# FRONT_PWR.net
KiCad netlist of a schematic drawn in Altium Designer
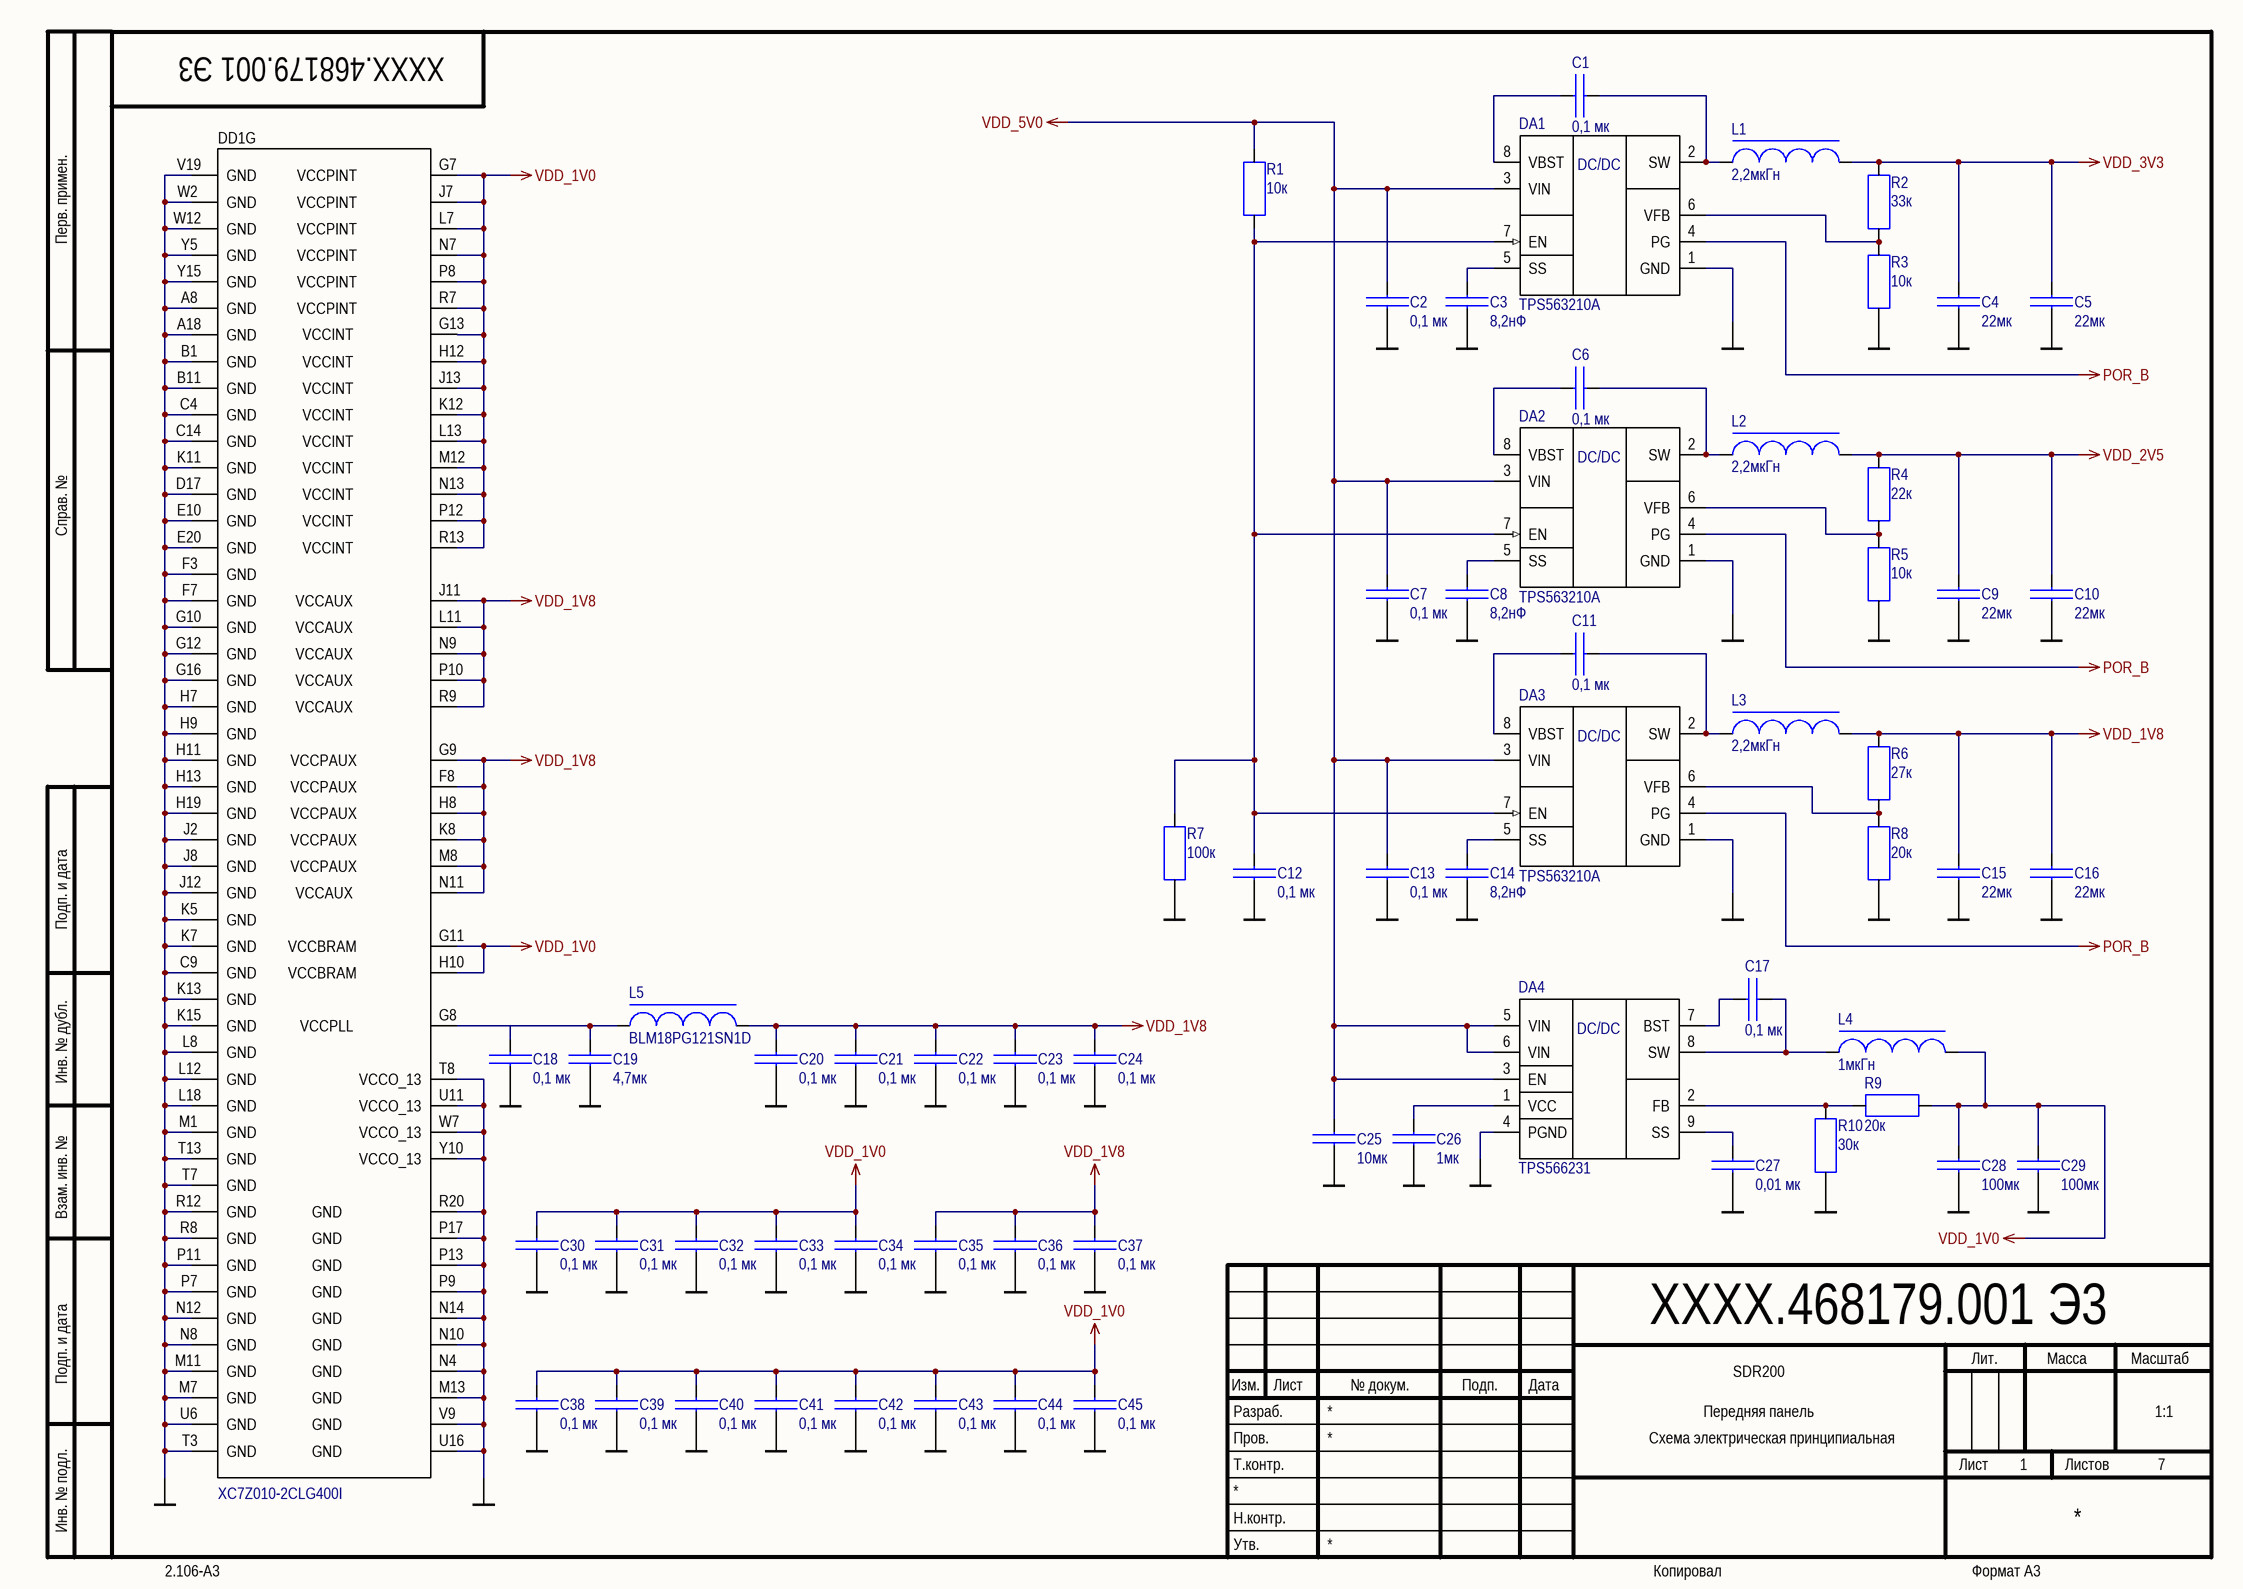
[diagram p0: FRONT_PWR.SchDoc]

(export (version "E")
  (design (tool "Eeschema 10.0.6"))
  (components
    (comp (ref "C1")
      (value "CC0402KRX5R6BB104")
      (footprint "CAPC1005X05L")
      (description "ЧИП конденсатор")
      (fields
        (field (name "NOMINAL") "0,1 мк")
        (field (name "MANUFACTURER") "Yageo")
        (field (name "TOLERANCE") "10%")
      )
      (libsource (lib "Database_Gost") (part "Capacitor const"))
    )
    (comp (ref "C2")
      (value "CC0402KRX5R6BB104")
      (footprint "CAPC1005X05L")
      (description "ЧИП конденсатор")
      (fields
        (field (name "NOMINAL") "0,1 мк")
        (field (name "MANUFACTURER") "Yageo")
        (field (name "TOLERANCE") "10%")
      )
      (libsource (lib "Database_Gost") (part "Capacitor const"))
    )
    (comp (ref "C3")
      (value "CC0402KRX7R9BB822")
      (footprint "CAPC1005X05L")
      (description "ЧИП конденсатор")
      (fields
        (field (name "NOMINAL") "8,2нФ")
        (field (name "MANUFACTURER") "Yageo")
        (field (name "TOLERANCE") "10%")
      )
      (libsource (lib "Database_Gost") (part "Capacitor const"))
    )
    (comp (ref "C4")
      (value "CC0805MKX5R5BB226")
      (footprint "CAPC2012X09L")
      (description "ЧИП конденсатор")
      (fields
        (field (name "NOMINAL") "22мк")
        (field (name "MANUFACTURER") "Yageo")
        (field (name "TOLERANCE") "0,2")
      )
      (libsource (lib "Database_Gost") (part "Capacitor const"))
    )
    (comp (ref "C5")
      (value "CC0805MKX5R5BB226")
      (footprint "CAPC2012X09L")
      (description "ЧИП конденсатор")
      (fields
        (field (name "NOMINAL") "22мк")
        (field (name "MANUFACTURER") "Yageo")
        (field (name "TOLERANCE") "0,2")
      )
      (libsource (lib "Database_Gost") (part "Capacitor const"))
    )
    (comp (ref "C6")
      (value "CC0402KRX5R6BB104")
      (footprint "CAPC1005X05L")
      (description "ЧИП конденсатор")
      (fields
        (field (name "NOMINAL") "0,1 мк")
        (field (name "MANUFACTURER") "Yageo")
        (field (name "TOLERANCE") "10%")
      )
      (libsource (lib "Database_Gost") (part "Capacitor const"))
    )
    (comp (ref "C7")
      (value "CC0402KRX5R6BB104")
      (footprint "CAPC1005X05L")
      (description "ЧИП конденсатор")
      (fields
        (field (name "NOMINAL") "0,1 мк")
        (field (name "MANUFACTURER") "Yageo")
        (field (name "TOLERANCE") "10%")
      )
      (libsource (lib "Database_Gost") (part "Capacitor const"))
    )
    (comp (ref "C8")
      (value "CC0402KRX7R9BB822")
      (footprint "CAPC1005X05L")
      (description "ЧИП конденсатор")
      (fields
        (field (name "NOMINAL") "8,2нФ")
        (field (name "MANUFACTURER") "Yageo")
        (field (name "TOLERANCE") "10%")
      )
      (libsource (lib "Database_Gost") (part "Capacitor const"))
    )
    (comp (ref "C9")
      (value "CC0805MKX5R5BB226")
      (footprint "CAPC2012X09L")
      (description "ЧИП конденсатор")
      (fields
        (field (name "NOMINAL") "22мк")
        (field (name "MANUFACTURER") "Yageo")
        (field (name "TOLERANCE") "0,2")
      )
      (libsource (lib "Database_Gost") (part "Capacitor const"))
    )
    (comp (ref "C10")
      (value "CC0805MKX5R5BB226")
      (footprint "CAPC2012X09L")
      (description "ЧИП конденсатор")
      (fields
        (field (name "NOMINAL") "22мк")
        (field (name "MANUFACTURER") "Yageo")
        (field (name "TOLERANCE") "0,2")
      )
      (libsource (lib "Database_Gost") (part "Capacitor const"))
    )
    (comp (ref "C11")
      (value "CC0402KRX5R6BB104")
      (footprint "CAPC1005X05L")
      (description "ЧИП конденсатор")
      (fields
        (field (name "NOMINAL") "0,1 мк")
        (field (name "MANUFACTURER") "Yageo")
        (field (name "TOLERANCE") "10%")
      )
      (libsource (lib "Database_Gost") (part "Capacitor const"))
    )
    (comp (ref "C12")
      (value "CC0402KRX5R6BB104")
      (footprint "CAPC1005X05L")
      (description "ЧИП конденсатор")
      (fields
        (field (name "NOMINAL") "0,1 мк")
        (field (name "MANUFACTURER") "Yageo")
        (field (name "TOLERANCE") "10%")
      )
      (libsource (lib "Database_Gost") (part "Capacitor const"))
    )
    (comp (ref "C13")
      (value "CC0402KRX5R6BB104")
      (footprint "CAPC1005X05L")
      (description "ЧИП конденсатор")
      (fields
        (field (name "NOMINAL") "0,1 мк")
        (field (name "MANUFACTURER") "Yageo")
        (field (name "TOLERANCE") "10%")
      )
      (libsource (lib "Database_Gost") (part "Capacitor const"))
    )
    (comp (ref "C14")
      (value "CC0402KRX7R9BB822")
      (footprint "CAPC1005X05L")
      (description "ЧИП конденсатор")
      (fields
        (field (name "NOMINAL") "8,2нФ")
        (field (name "MANUFACTURER") "Yageo")
        (field (name "TOLERANCE") "10%")
      )
      (libsource (lib "Database_Gost") (part "Capacitor const"))
    )
    (comp (ref "C15")
      (value "CC0805MKX5R5BB226")
      (footprint "CAPC2012X09L")
      (description "ЧИП конденсатор")
      (fields
        (field (name "NOMINAL") "22мк")
        (field (name "MANUFACTURER") "Yageo")
        (field (name "TOLERANCE") "0,2")
      )
      (libsource (lib "Database_Gost") (part "Capacitor const"))
    )
    (comp (ref "C16")
      (value "CC0805MKX5R5BB226")
      (footprint "CAPC2012X09L")
      (description "ЧИП конденсатор")
      (fields
        (field (name "NOMINAL") "22мк")
        (field (name "MANUFACTURER") "Yageo")
        (field (name "TOLERANCE") "0,2")
      )
      (libsource (lib "Database_Gost") (part "Capacitor const"))
    )
    (comp (ref "C17")
      (value "CC0402KRX5R6BB104")
      (footprint "CAPC1005X05L")
      (description "ЧИП конденсатор")
      (fields
        (field (name "NOMINAL") "0,1 мк")
        (field (name "MANUFACTURER") "Yageo")
        (field (name "TOLERANCE") "10%")
      )
      (libsource (lib "Database_Gost") (part "Capacitor const"))
    )
    (comp (ref "C18")
      (value "CC0402KRX5R6BB104")
      (footprint "CAPC1005X05L")
      (description "ЧИП конденсатор")
      (fields
        (field (name "NOMINAL") "0,1 мк")
        (field (name "MANUFACTURER") "Yageo")
        (field (name "TOLERANCE") "10%")
      )
      (libsource (lib "Database_Gost") (part "Capacitor const"))
    )
    (comp (ref "C19")
      (value "CC0603KRX5R6BB475")
      (footprint "CAPC1608X08L")
      (description "ЧИП конденсатор")
      (fields
        (field (name "NOMINAL") "4,7мк")
        (field (name "MANUFACTURER") "Yageo")
        (field (name "TOLERANCE") "10%")
      )
      (libsource (lib "Database_Gost") (part "Capacitor const"))
    )
    (comp (ref "C20")
      (value "CC0402KRX5R6BB104")
      (footprint "CAPC1005X05L")
      (description "ЧИП конденсатор")
      (fields
        (field (name "NOMINAL") "0,1 мк")
        (field (name "MANUFACTURER") "Yageo")
        (field (name "TOLERANCE") "10%")
      )
      (libsource (lib "Database_Gost") (part "Capacitor const"))
    )
    (comp (ref "C21")
      (value "CC0402KRX5R6BB104")
      (footprint "CAPC1005X05L")
      (description "ЧИП конденсатор")
      (fields
        (field (name "NOMINAL") "0,1 мк")
        (field (name "MANUFACTURER") "Yageo")
        (field (name "TOLERANCE") "10%")
      )
      (libsource (lib "Database_Gost") (part "Capacitor const"))
    )
    (comp (ref "C22")
      (value "CC0402KRX5R6BB104")
      (footprint "CAPC1005X05L")
      (description "ЧИП конденсатор")
      (fields
        (field (name "NOMINAL") "0,1 мк")
        (field (name "MANUFACTURER") "Yageo")
        (field (name "TOLERANCE") "10%")
      )
      (libsource (lib "Database_Gost") (part "Capacitor const"))
    )
    (comp (ref "C23")
      (value "CC0402KRX5R6BB104")
      (footprint "CAPC1005X05L")
      (description "ЧИП конденсатор")
      (fields
        (field (name "NOMINAL") "0,1 мк")
        (field (name "MANUFACTURER") "Yageo")
        (field (name "TOLERANCE") "10%")
      )
      (libsource (lib "Database_Gost") (part "Capacitor const"))
    )
    (comp (ref "C24")
      (value "CC0402KRX5R6BB104")
      (footprint "CAPC1005X05L")
      (description "ЧИП конденсатор")
      (fields
        (field (name "NOMINAL") "0,1 мк")
        (field (name "MANUFACTURER") "Yageo")
        (field (name "TOLERANCE") "10%")
      )
      (libsource (lib "Database_Gost") (part "Capacitor const"))
    )
    (comp (ref "C25")
      (value "CC0805KKX5R8BB106")
      (footprint "CAPC2012X09L")
      (description "ЧИП конденсатор")
      (fields
        (field (name "NOMINAL") "10мк")
        (field (name "MANUFACTURER") "Yageo")
        (field (name "TOLERANCE") "0,1")
      )
      (libsource (lib "Database_Gost") (part "Capacitor const"))
    )
    (comp (ref "C26")
      (value "CC0402KRX5R5BB105")
      (footprint "CAPC1005X05L")
      (description "ЧИП конденсатор")
      (fields
        (field (name "NOMINAL") "1мк")
        (field (name "MANUFACTURER") "Yageo")
        (field (name "TOLERANCE") "10%")
      )
      (libsource (lib "Database_Gost") (part "Capacitor const"))
    )
    (comp (ref "C27")
      (value "CC0402KRX7R9BB103")
      (footprint "CAPC1005X05L")
      (description "ЧИП конденсатор")
      (fields
        (field (name "NOMINAL") "0,01 мк")
        (field (name "MANUFACTURER") "Yageo")
        (field (name "TOLERANCE") "10%")
      )
      (libsource (lib "Database_Gost") (part "Capacitor const"))
    )
    (comp (ref "C28")
      (value "CC1206MKX5R5BB107")
      (footprint "CAPC3216X12L")
      (description "ЧИП конденсатор")
      (fields
        (field (name "NOMINAL") "100мк")
        (field (name "MANUFACTURER") "Yageo")
        (field (name "TOLERANCE") "20%")
      )
      (libsource (lib "Database_Gost") (part "Capacitor const"))
    )
    (comp (ref "C29")
      (value "CC1206MKX5R5BB107")
      (footprint "CAPC3216X12L")
      (description "ЧИП конденсатор")
      (fields
        (field (name "NOMINAL") "100мк")
        (field (name "MANUFACTURER") "Yageo")
        (field (name "TOLERANCE") "20%")
      )
      (libsource (lib "Database_Gost") (part "Capacitor const"))
    )
    (comp (ref "C30")
      (value "CC0402KRX5R6BB104")
      (footprint "CAPC1005X05L")
      (description "ЧИП конденсатор")
      (fields
        (field (name "NOMINAL") "0,1 мк")
        (field (name "MANUFACTURER") "Yageo")
        (field (name "TOLERANCE") "10%")
      )
      (libsource (lib "Database_Gost") (part "Capacitor const"))
    )
    (comp (ref "C31")
      (value "CC0402KRX5R6BB104")
      (footprint "CAPC1005X05L")
      (description "ЧИП конденсатор")
      (fields
        (field (name "NOMINAL") "0,1 мк")
        (field (name "MANUFACTURER") "Yageo")
        (field (name "TOLERANCE") "10%")
      )
      (libsource (lib "Database_Gost") (part "Capacitor const"))
    )
    (comp (ref "C32")
      (value "CC0402KRX5R6BB104")
      (footprint "CAPC1005X05L")
      (description "ЧИП конденсатор")
      (fields
        (field (name "NOMINAL") "0,1 мк")
        (field (name "MANUFACTURER") "Yageo")
        (field (name "TOLERANCE") "10%")
      )
      (libsource (lib "Database_Gost") (part "Capacitor const"))
    )
    (comp (ref "C33")
      (value "CC0402KRX5R6BB104")
      (footprint "CAPC1005X05L")
      (description "ЧИП конденсатор")
      (fields
        (field (name "NOMINAL") "0,1 мк")
        (field (name "MANUFACTURER") "Yageo")
        (field (name "TOLERANCE") "10%")
      )
      (libsource (lib "Database_Gost") (part "Capacitor const"))
    )
    (comp (ref "C34")
      (value "CC0402KRX5R6BB104")
      (footprint "CAPC1005X05L")
      (description "ЧИП конденсатор")
      (fields
        (field (name "NOMINAL") "0,1 мк")
        (field (name "MANUFACTURER") "Yageo")
        (field (name "TOLERANCE") "10%")
      )
      (libsource (lib "Database_Gost") (part "Capacitor const"))
    )
    (comp (ref "C35")
      (value "CC0402KRX5R6BB104")
      (footprint "CAPC1005X05L")
      (description "ЧИП конденсатор")
      (fields
        (field (name "NOMINAL") "0,1 мк")
        (field (name "MANUFACTURER") "Yageo")
        (field (name "TOLERANCE") "10%")
      )
      (libsource (lib "Database_Gost") (part "Capacitor const"))
    )
    (comp (ref "C36")
      (value "CC0402KRX5R6BB104")
      (footprint "CAPC1005X05L")
      (description "ЧИП конденсатор")
      (fields
        (field (name "NOMINAL") "0,1 мк")
        (field (name "MANUFACTURER") "Yageo")
        (field (name "TOLERANCE") "10%")
      )
      (libsource (lib "Database_Gost") (part "Capacitor const"))
    )
    (comp (ref "C37")
      (value "CC0402KRX5R6BB104")
      (footprint "CAPC1005X05L")
      (description "ЧИП конденсатор")
      (fields
        (field (name "NOMINAL") "0,1 мк")
        (field (name "MANUFACTURER") "Yageo")
        (field (name "TOLERANCE") "10%")
      )
      (libsource (lib "Database_Gost") (part "Capacitor const"))
    )
    (comp (ref "C38")
      (value "CC0402KRX5R6BB104")
      (footprint "CAPC1005X05L")
      (description "ЧИП конденсатор")
      (fields
        (field (name "NOMINAL") "0,1 мк")
        (field (name "MANUFACTURER") "Yageo")
        (field (name "TOLERANCE") "10%")
      )
      (libsource (lib "Database_Gost") (part "Capacitor const"))
    )
    (comp (ref "C39")
      (value "CC0402KRX5R6BB104")
      (footprint "CAPC1005X05L")
      (description "ЧИП конденсатор")
      (fields
        (field (name "NOMINAL") "0,1 мк")
        (field (name "MANUFACTURER") "Yageo")
        (field (name "TOLERANCE") "10%")
      )
      (libsource (lib "Database_Gost") (part "Capacitor const"))
    )
    (comp (ref "C40")
      (value "CC0402KRX5R6BB104")
      (footprint "CAPC1005X05L")
      (description "ЧИП конденсатор")
      (fields
        (field (name "NOMINAL") "0,1 мк")
        (field (name "MANUFACTURER") "Yageo")
        (field (name "TOLERANCE") "10%")
      )
      (libsource (lib "Database_Gost") (part "Capacitor const"))
    )
    (comp (ref "C41")
      (value "CC0402KRX5R6BB104")
      (footprint "CAPC1005X05L")
      (description "ЧИП конденсатор")
      (fields
        (field (name "NOMINAL") "0,1 мк")
        (field (name "MANUFACTURER") "Yageo")
        (field (name "TOLERANCE") "10%")
      )
      (libsource (lib "Database_Gost") (part "Capacitor const"))
    )
    (comp (ref "C42")
      (value "CC0402KRX5R6BB104")
      (footprint "CAPC1005X05L")
      (description "ЧИП конденсатор")
      (fields
        (field (name "NOMINAL") "0,1 мк")
        (field (name "MANUFACTURER") "Yageo")
        (field (name "TOLERANCE") "10%")
      )
      (libsource (lib "Database_Gost") (part "Capacitor const"))
    )
    (comp (ref "C43")
      (value "CC0402KRX5R6BB104")
      (footprint "CAPC1005X05L")
      (description "ЧИП конденсатор")
      (fields
        (field (name "NOMINAL") "0,1 мк")
        (field (name "MANUFACTURER") "Yageo")
        (field (name "TOLERANCE") "10%")
      )
      (libsource (lib "Database_Gost") (part "Capacitor const"))
    )
    (comp (ref "C44")
      (value "CC0402KRX5R6BB104")
      (footprint "CAPC1005X05L")
      (description "ЧИП конденсатор")
      (fields
        (field (name "NOMINAL") "0,1 мк")
        (field (name "MANUFACTURER") "Yageo")
        (field (name "TOLERANCE") "10%")
      )
      (libsource (lib "Database_Gost") (part "Capacitor const"))
    )
    (comp (ref "C45")
      (value "CC0402KRX5R6BB104")
      (footprint "CAPC1005X05L")
      (description "ЧИП конденсатор")
      (fields
        (field (name "NOMINAL") "0,1 мк")
        (field (name "MANUFACTURER") "Yageo")
        (field (name "TOLERANCE") "10%")
      )
      (libsource (lib "Database_Gost") (part "Capacitor const"))
    )
    (comp (ref "DA1")
      (value "TPS563210A")
      (footprint "TSOP65P280X110-8L")
      (description "TPS56x210A, 4.5-V to 17-V Input, 2-A, 3-A Synchrono")
      (fields (field (name "MANUFACTURER") "TI"))
      (libsource (lib "Chips_single") (part "TPS563210A"))
    )
    (comp (ref "DA2")
      (value "TPS563210A")
      (footprint "TSOP65P280X110-8L")
      (description "TPS56x210A, 4.5-V to 17-V Input, 2-A, 3-A Synchrono")
      (fields (field (name "MANUFACTURER") "TI"))
      (libsource (lib "Chips_single") (part "TPS563210A"))
    )
    (comp (ref "DA3")
      (value "TPS563210A")
      (footprint "TSOP65P280X110-8L")
      (description "TPS56x210A, 4.5-V to 17-V Input, 2-A, 3-A Synchrono")
      (fields (field (name "MANUFACTURER") "TI"))
      (libsource (lib "Chips_single") (part "TPS563210A"))
    )
    (comp (ref "DA4")
      (value "TPS566231")
      (footprint "VQFN-HR 9")
      (description "3-V to 18-V Input, 6-A Synchronous Step-Down Voltage Regulator")
      (libsource (lib "Chips_single") (part "TPS566231"))
    )
    (comp (ref "DD1")
      (value "XC7Z010-2CLG400I")
      (footprint "BGA400C80P20X20_1700X1700X147")
      (description "Zynq®-7000 SoC Family")
      (fields (field (name "MANUFACTURER") "Xilinx"))
      (libsource (lib "Chips_single") (part "XC7Z010-2CLG400I"))
    )
    (comp (ref "L1")
      (value "XGL4020-222ME")
      (footprint "INDCXGL4020")
      (description "Shielded Power Inductors")
      (fields (field (name "NOMINAL") "2,2мкГн") (field (name "MANUFACTURER") "Coilcraft"))
      (libsource (lib "Database_Gost") (part "Inductor ferr"))
    )
    (comp (ref "L2")
      (value "XGL4020-222ME")
      (footprint "INDCXGL4020")
      (description "Shielded Power Inductors")
      (fields (field (name "NOMINAL") "2,2мкГн") (field (name "MANUFACTURER") "Coilcraft"))
      (libsource (lib "Database_Gost") (part "Inductor ferr"))
    )
    (comp (ref "L3")
      (value "XGL4020-222ME")
      (footprint "INDCXGL4020")
      (description "Shielded Power Inductors")
      (fields (field (name "NOMINAL") "2,2мкГн") (field (name "MANUFACTURER") "Coilcraft"))
      (libsource (lib "Database_Gost") (part "Inductor ferr"))
    )
    (comp (ref "L4")
      (value "XGL4020-102ME")
      (footprint "INDCXGL4020")
      (description "Shielded Power Inductors")
      (fields (field (name "NOMINAL") "1мкГн") (field (name "MANUFACTURER") "Coilcraft"))
      (libsource (lib "Database_Gost") (part "Inductor ferr"))
    )
    (comp (ref "L5")
      (value "BLM18PG121SN1D")
      (footprint "INDC1608X05L")
      (description "Chip Ferrite Beads (0603 Size)")
      (fields (field (name "NOMINAL") "BLM18PG121SN1D") (field (name "MANUFACTURER") "Murata"))
      (libsource (lib "Database_Gost") (part "Inductor ferr"))
    )
    (comp (ref "R1")
      (value "RC0402JR-0710KL")
      (footprint "RESC1005X04L")
      (description "ЧИП резистор")
      (fields
        (field (name "NOMINAL") "10к")
        (field (name "MANUFACTURER") "Yageo")
        (field (name "TOLERANCE") "5%")
      )
      (libsource (lib "Database_Gost") (part "Resistor const"))
    )
    (comp (ref "R2")
      (value "RC0402JR-0733KL")
      (footprint "RESC1005X04L")
      (description "ЧИП резистор")
      (fields
        (field (name "NOMINAL") "33к")
        (field (name "MANUFACTURER") "Yageo")
        (field (name "TOLERANCE") "5%")
      )
      (libsource (lib "Database_Gost") (part "Resistor const"))
    )
    (comp (ref "R3")
      (value "RC0402JR-0710KL")
      (footprint "RESC1005X04L")
      (description "ЧИП резистор")
      (fields
        (field (name "NOMINAL") "10к")
        (field (name "MANUFACTURER") "Yageo")
        (field (name "TOLERANCE") "5%")
      )
      (libsource (lib "Database_Gost") (part "Resistor const"))
    )
    (comp (ref "R4")
      (value "RC0402JR-0722KL")
      (footprint "RESC1005X04L")
      (description "ЧИП резистор")
      (fields
        (field (name "NOMINAL") "22к")
        (field (name "MANUFACTURER") "Yageo")
        (field (name "TOLERANCE") "5%")
      )
      (libsource (lib "Database_Gost") (part "Resistor const"))
    )
    (comp (ref "R5")
      (value "RC0402JR-0710KL")
      (footprint "RESC1005X04L")
      (description "ЧИП резистор")
      (fields
        (field (name "NOMINAL") "10к")
        (field (name "MANUFACTURER") "Yageo")
        (field (name "TOLERANCE") "5%")
      )
      (libsource (lib "Database_Gost") (part "Resistor const"))
    )
    (comp (ref "R6")
      (value "RC0402JR-0727KL")
      (footprint "RESC1005X04L")
      (description "ЧИП резистор")
      (fields
        (field (name "NOMINAL") "27к")
        (field (name "MANUFACTURER") "Yageo")
        (field (name "TOLERANCE") "5%")
      )
      (libsource (lib "Database_Gost") (part "Resistor const"))
    )
    (comp (ref "R7")
      (value "RC0402JR-07100KL")
      (footprint "RESC1005X04L")
      (description "ЧИП резистор")
      (fields
        (field (name "NOMINAL") "100к")
        (field (name "MANUFACTURER") "Yageo")
        (field (name "TOLERANCE") "5%")
      )
      (libsource (lib "Database_Gost") (part "Resistor const"))
    )
    (comp (ref "R8")
      (value "RC0402JR-0720KL")
      (footprint "RESC1005X04L")
      (description "ЧИП резистор")
      (fields
        (field (name "NOMINAL") "20к")
        (field (name "MANUFACTURER") "Yageo")
        (field (name "TOLERANCE") "5%")
      )
      (libsource (lib "Database_Gost") (part "Resistor const"))
    )
    (comp (ref "R9")
      (value "RC0402JR-0720KL")
      (footprint "RESC1005X04L")
      (description "ЧИП резистор")
      (fields
        (field (name "NOMINAL") "20к")
        (field (name "MANUFACTURER") "Yageo")
        (field (name "TOLERANCE") "5%")
      )
      (libsource (lib "Database_Gost") (part "Resistor const"))
    )
    (comp (ref "R10")
      (value "RC0402JR-0730KL")
      (footprint "RESC1005X04L")
      (description "ЧИП резистор")
      (fields
        (field (name "NOMINAL") "30к")
        (field (name "MANUFACTURER") "Yageo")
        (field (name "TOLERANCE") "5%")
      )
      (libsource (lib "Database_Gost") (part "Resistor const"))
    )
  )
  (nets
    (net (code "1") (name "GND") (class "Default")
      (node (ref "C10") (pin "1") (pinfunction "1_1") (pintype "passive"))
      (node (ref "C12") (pin "1") (pinfunction "1_1") (pintype "passive"))
      (node (ref "C13") (pin "1") (pinfunction "1_1") (pintype "passive"))
      (node (ref "C14") (pin "1") (pinfunction "1_1") (pintype "passive"))
      (node (ref "C15") (pin "1") (pinfunction "1_1") (pintype "passive"))
      (node (ref "C16") (pin "1") (pinfunction "1_1") (pintype "passive"))
      (node (ref "C18") (pin "2") (pinfunction "2_2") (pintype "passive"))
      (node (ref "C19") (pin "1") (pinfunction "1_1") (pintype "passive"))
      (node (ref "C2") (pin "1") (pinfunction "1_1") (pintype "passive"))
      (node (ref "C20") (pin "2") (pinfunction "2_2") (pintype "passive"))
      (node (ref "C21") (pin "2") (pinfunction "2_2") (pintype "passive"))
      (node (ref "C22") (pin "2") (pinfunction "2_2") (pintype "passive"))
      (node (ref "C23") (pin "2") (pinfunction "2_2") (pintype "passive"))
      (node (ref "C24") (pin "2") (pinfunction "2_2") (pintype "passive"))
      (node (ref "C25") (pin "1") (pinfunction "1_1") (pintype "passive"))
      (node (ref "C26") (pin "1") (pinfunction "1_1") (pintype "passive"))
      (node (ref "C27") (pin "1") (pinfunction "1_1") (pintype "passive"))
      (node (ref "C28") (pin "1") (pinfunction "1_1") (pintype "passive"))
      (node (ref "C29") (pin "1") (pinfunction "1_1") (pintype "passive"))
      (node (ref "C3") (pin "1") (pinfunction "1_1") (pintype "passive"))
      (node (ref "C30") (pin "2") (pinfunction "2_2") (pintype "passive"))
      (node (ref "C31") (pin "2") (pinfunction "2_2") (pintype "passive"))
      (node (ref "C32") (pin "2") (pinfunction "2_2") (pintype "passive"))
      (node (ref "C33") (pin "2") (pinfunction "2_2") (pintype "passive"))
      (node (ref "C34") (pin "2") (pinfunction "2_2") (pintype "passive"))
      (node (ref "C35") (pin "2") (pinfunction "2_2") (pintype "passive"))
      (node (ref "C36") (pin "2") (pinfunction "2_2") (pintype "passive"))
      (node (ref "C37") (pin "2") (pinfunction "2_2") (pintype "passive"))
      (node (ref "C38") (pin "2") (pinfunction "2_2") (pintype "passive"))
      (node (ref "C39") (pin "2") (pinfunction "2_2") (pintype "passive"))
      (node (ref "C4") (pin "1") (pinfunction "1_1") (pintype "passive"))
      (node (ref "C40") (pin "2") (pinfunction "2_2") (pintype "passive"))
      (node (ref "C41") (pin "2") (pinfunction "2_2") (pintype "passive"))
      (node (ref "C42") (pin "2") (pinfunction "2_2") (pintype "passive"))
      (node (ref "C43") (pin "2") (pinfunction "2_2") (pintype "passive"))
      (node (ref "C44") (pin "2") (pinfunction "2_2") (pintype "passive"))
      (node (ref "C45") (pin "2") (pinfunction "2_2") (pintype "passive"))
      (node (ref "C5") (pin "1") (pinfunction "1_1") (pintype "passive"))
      (node (ref "C7") (pin "1") (pinfunction "1_1") (pintype "passive"))
      (node (ref "C8") (pin "1") (pinfunction "1_1") (pintype "passive"))
      (node (ref "C9") (pin "1") (pinfunction "1_1") (pintype "passive"))
      (node (ref "DA1") (pin "1") (pinfunction "GND_1") (pintype "passive"))
      (node (ref "DA2") (pin "1") (pinfunction "GND_1") (pintype "passive"))
      (node (ref "DA3") (pin "1") (pinfunction "GND_1") (pintype "passive"))
      (node (ref "DA4") (pin "4") (pinfunction "PGND_4") (pintype "passive"))
      (node (ref "DD1") (pin "A18") (pinfunction "GND_A18") (pintype "power_in"))
      (node (ref "DD1") (pin "A8") (pinfunction "GND_A8") (pintype "power_in"))
      (node (ref "DD1") (pin "B1") (pinfunction "GND_B1") (pintype "power_in"))
      (node (ref "DD1") (pin "B11") (pinfunction "GND_B11") (pintype "power_in"))
      (node (ref "DD1") (pin "C14") (pinfunction "GND_C14") (pintype "power_in"))
      (node (ref "DD1") (pin "C4") (pinfunction "GND_C4") (pintype "power_in"))
      (node (ref "DD1") (pin "C9") (pinfunction "GND_C9") (pintype "power_in"))
      (node (ref "DD1") (pin "D17") (pinfunction "GND_D17") (pintype "power_in"))
      (node (ref "DD1") (pin "E10") (pinfunction "GND_E10") (pintype "power_in"))
      (node (ref "DD1") (pin "E20") (pinfunction "GND_E20") (pintype "power_in"))
      (node (ref "DD1") (pin "F3") (pinfunction "GND_F3") (pintype "power_in"))
      (node (ref "DD1") (pin "F7") (pinfunction "GND_F7") (pintype "power_in"))
      (node (ref "DD1") (pin "G10") (pinfunction "GND_G10") (pintype "power_in"))
      (node (ref "DD1") (pin "G12") (pinfunction "GND_G12") (pintype "power_in"))
      (node (ref "DD1") (pin "G16") (pinfunction "GND_G16") (pintype "power_in"))
      (node (ref "DD1") (pin "H11") (pinfunction "GND_H11") (pintype "power_in"))
      (node (ref "DD1") (pin "H13") (pinfunction "GND_H13") (pintype "power_in"))
      (node (ref "DD1") (pin "H19") (pinfunction "GND_H19") (pintype "power_in"))
      (node (ref "DD1") (pin "H7") (pinfunction "GND_H7") (pintype "power_in"))
      (node (ref "DD1") (pin "H9") (pinfunction "GND_H9") (pintype "power_in"))
      (node (ref "DD1") (pin "J12") (pinfunction "GND_J12") (pintype "power_in"))
      (node (ref "DD1") (pin "J2") (pinfunction "GND_J2") (pintype "power_in"))
      (node (ref "DD1") (pin "J8") (pinfunction "GND_J8") (pintype "power_in"))
      (node (ref "DD1") (pin "K11") (pinfunction "GND_K11") (pintype "power_in"))
      (node (ref "DD1") (pin "K13") (pinfunction "GND_K13") (pintype "power_in"))
      (node (ref "DD1") (pin "K15") (pinfunction "GND_K15") (pintype "power_in"))
      (node (ref "DD1") (pin "K5") (pinfunction "GND_K5") (pintype "power_in"))
      (node (ref "DD1") (pin "K7") (pinfunction "GND_K7") (pintype "power_in"))
      (node (ref "DD1") (pin "L12") (pinfunction "GND_L12") (pintype "power_in"))
      (node (ref "DD1") (pin "L18") (pinfunction "GND_L18") (pintype "power_in"))
      (node (ref "DD1") (pin "L8") (pinfunction "GND_L8") (pintype "power_in"))
      (node (ref "DD1") (pin "M1") (pinfunction "GND_M1") (pintype "power_in"))
      (node (ref "DD1") (pin "M11") (pinfunction "GND_M11") (pintype "power_in"))
      (node (ref "DD1") (pin "M13") (pinfunction "GND_M13") (pintype "power_in"))
      (node (ref "DD1") (pin "M7") (pinfunction "GND_M7") (pintype "power_in"))
      (node (ref "DD1") (pin "N10") (pinfunction "GND_N10") (pintype "power_in"))
      (node (ref "DD1") (pin "N12") (pinfunction "GND_N12") (pintype "power_in"))
      (node (ref "DD1") (pin "N14") (pinfunction "GND_N14") (pintype "power_in"))
      (node (ref "DD1") (pin "N4") (pinfunction "GND_N4") (pintype "power_in"))
      (node (ref "DD1") (pin "N8") (pinfunction "GND_N8") (pintype "power_in"))
      (node (ref "DD1") (pin "P11") (pinfunction "GND_P11") (pintype "power_in"))
      (node (ref "DD1") (pin "P13") (pinfunction "GND_P13") (pintype "power_in"))
      (node (ref "DD1") (pin "P17") (pinfunction "GND_P17") (pintype "power_in"))
      (node (ref "DD1") (pin "P7") (pinfunction "GND_P7") (pintype "power_in"))
      (node (ref "DD1") (pin "P9") (pinfunction "GND_P9") (pintype "power_in"))
      (node (ref "DD1") (pin "R12") (pinfunction "GND_R12") (pintype "power_in"))
      (node (ref "DD1") (pin "R20") (pinfunction "GND_R20") (pintype "power_in"))
      (node (ref "DD1") (pin "R8") (pinfunction "GND_R8") (pintype "power_in"))
      (node (ref "DD1") (pin "T13") (pinfunction "GND_T13") (pintype "power_in"))
      (node (ref "DD1") (pin "T3") (pinfunction "GND_T3") (pintype "power_in"))
      (node (ref "DD1") (pin "T7") (pinfunction "GND_T7") (pintype "power_in"))
      (node (ref "DD1") (pin "T8") (pinfunction "VCCO_13_T8") (pintype "power_in"))
      (node (ref "DD1") (pin "U11") (pinfunction "VCCO_13_U11") (pintype "power_in"))
      (node (ref "DD1") (pin "U16") (pinfunction "GND_U16") (pintype "power_in"))
      (node (ref "DD1") (pin "U6") (pinfunction "GND_U6") (pintype "power_in"))
      (node (ref "DD1") (pin "V19") (pinfunction "GND_V19") (pintype "power_in"))
      (node (ref "DD1") (pin "V9") (pinfunction "GND_V9") (pintype "power_in"))
      (node (ref "DD1") (pin "W12") (pinfunction "GND_W12") (pintype "power_in"))
      (node (ref "DD1") (pin "W2") (pinfunction "GND_W2") (pintype "power_in"))
      (node (ref "DD1") (pin "W7") (pinfunction "VCCO_13_W7") (pintype "power_in"))
      (node (ref "DD1") (pin "Y10") (pinfunction "VCCO_13_Y10") (pintype "power_in"))
      (node (ref "DD1") (pin "Y15") (pinfunction "GND_Y15") (pintype "power_in"))
      (node (ref "DD1") (pin "Y5") (pinfunction "GND_Y5") (pintype "power_in"))
      (node (ref "R10") (pin "1") (pinfunction "1_1") (pintype "passive"))
      (node (ref "R3") (pin "2") (pinfunction "2_2") (pintype "passive"))
      (node (ref "R5") (pin "2") (pinfunction "2_2") (pintype "passive"))
      (node (ref "R7") (pin "1") (pinfunction "1_1") (pintype "passive"))
      (node (ref "R8") (pin "2") (pinfunction "2_2") (pintype "passive"))
    )
    (net (code "2") (name "Net-(DA1-EN)") (class "Default")
      (node (ref "C12") (pin "2") (pinfunction "2_2") (pintype "passive"))
      (node (ref "DA1") (pin "7") (pinfunction "EN_7") (pintype "input"))
      (node (ref "DA2") (pin "7") (pinfunction "EN_7") (pintype "input"))
      (node (ref "DA3") (pin "7") (pinfunction "EN_7") (pintype "input"))
      (node (ref "R1") (pin "2") (pinfunction "2_2") (pintype "passive"))
      (node (ref "R7") (pin "2") (pinfunction "2_2") (pintype "passive"))
    )
    (net (code "3") (name "Net-(DA1-SS)") (class "Default")
      (node (ref "C3") (pin "2") (pinfunction "2_2") (pintype "passive"))
      (node (ref "DA1") (pin "5") (pinfunction "SS_5") (pintype "passive"))
    )
    (net (code "4") (name "Net-(DA1-SW)") (class "Default")
      (node (ref "C1") (pin "2") (pinfunction "2_2") (pintype "passive"))
      (node (ref "DA1") (pin "2") (pinfunction "SW_2") (pintype "passive"))
      (node (ref "L1") (pin "2") (pinfunction "2_2") (pintype "passive"))
    )
    (net (code "5") (name "Net-(DA1-VBST)") (class "Default")
      (node (ref "C1") (pin "1") (pinfunction "1_1") (pintype "passive"))
      (node (ref "DA1") (pin "8") (pinfunction "VBST_8") (pintype "passive"))
    )
    (net (code "6") (name "Net-(DA1-VFB)") (class "Default")
      (node (ref "DA1") (pin "6") (pinfunction "VFB_6") (pintype "passive"))
      (node (ref "R2") (pin "2") (pinfunction "2_2") (pintype "passive"))
      (node (ref "R3") (pin "1") (pinfunction "1_1") (pintype "passive"))
    )
    (net (code "7") (name "Net-(DA2-SS)") (class "Default")
      (node (ref "C8") (pin "2") (pinfunction "2_2") (pintype "passive"))
      (node (ref "DA2") (pin "5") (pinfunction "SS_5") (pintype "passive"))
    )
    (net (code "8") (name "Net-(DA2-SW)") (class "Default")
      (node (ref "C6") (pin "2") (pinfunction "2_2") (pintype "passive"))
      (node (ref "DA2") (pin "2") (pinfunction "SW_2") (pintype "passive"))
      (node (ref "L2") (pin "2") (pinfunction "2_2") (pintype "passive"))
    )
    (net (code "9") (name "Net-(DA2-VBST)") (class "Default")
      (node (ref "C6") (pin "1") (pinfunction "1_1") (pintype "passive"))
      (node (ref "DA2") (pin "8") (pinfunction "VBST_8") (pintype "passive"))
    )
    (net (code "10") (name "Net-(DA2-VFB)") (class "Default")
      (node (ref "DA2") (pin "6") (pinfunction "VFB_6") (pintype "passive"))
      (node (ref "R4") (pin "2") (pinfunction "2_2") (pintype "passive"))
      (node (ref "R5") (pin "1") (pinfunction "1_1") (pintype "passive"))
    )
    (net (code "11") (name "Net-(DA3-SS)") (class "Default")
      (node (ref "C14") (pin "2") (pinfunction "2_2") (pintype "passive"))
      (node (ref "DA3") (pin "5") (pinfunction "SS_5") (pintype "passive"))
    )
    (net (code "12") (name "Net-(DA3-SW)") (class "Default")
      (node (ref "C11") (pin "2") (pinfunction "2_2") (pintype "passive"))
      (node (ref "DA3") (pin "2") (pinfunction "SW_2") (pintype "passive"))
      (node (ref "L3") (pin "2") (pinfunction "2_2") (pintype "passive"))
    )
    (net (code "13") (name "Net-(DA3-VBST)") (class "Default")
      (node (ref "C11") (pin "1") (pinfunction "1_1") (pintype "passive"))
      (node (ref "DA3") (pin "8") (pinfunction "VBST_8") (pintype "passive"))
    )
    (net (code "14") (name "Net-(DA3-VFB)") (class "Default")
      (node (ref "DA3") (pin "6") (pinfunction "VFB_6") (pintype "passive"))
      (node (ref "R6") (pin "2") (pinfunction "2_2") (pintype "passive"))
      (node (ref "R8") (pin "1") (pinfunction "1_1") (pintype "passive"))
    )
    (net (code "15") (name "Net-(DA4-BST)") (class "Default")
      (node (ref "C17") (pin "1") (pinfunction "1_1") (pintype "passive"))
      (node (ref "DA4") (pin "7") (pinfunction "BST_7") (pintype "passive"))
    )
    (net (code "16") (name "Net-(DA4-FB)") (class "Default")
      (node (ref "DA4") (pin "2") (pinfunction "FB_2") (pintype "passive"))
      (node (ref "R10") (pin "2") (pinfunction "2_2") (pintype "passive"))
      (node (ref "R9") (pin "2") (pinfunction "2_2") (pintype "passive"))
    )
    (net (code "17") (name "Net-(DA4-SS)") (class "Default")
      (node (ref "C27") (pin "2") (pinfunction "2_2") (pintype "passive"))
      (node (ref "DA4") (pin "9") (pinfunction "SS_9") (pintype "passive"))
    )
    (net (code "18") (name "Net-(DA4-SW)") (class "Default")
      (node (ref "C17") (pin "2") (pinfunction "2_2") (pintype "passive"))
      (node (ref "DA4") (pin "8") (pinfunction "SW_8") (pintype "passive"))
      (node (ref "L4") (pin "2") (pinfunction "2_2") (pintype "passive"))
    )
    (net (code "19") (name "Net-(DA4-VCC)") (class "Default")
      (node (ref "C26") (pin "2") (pinfunction "2_2") (pintype "passive"))
      (node (ref "DA4") (pin "1") (pinfunction "VCC_1") (pintype "passive"))
    )
    (net (code "20") (name "Net-(DD1G-VCCPLL)") (class "Default")
      (node (ref "C18") (pin "1") (pinfunction "1_1") (pintype "passive"))
      (node (ref "C19") (pin "2") (pinfunction "2_2") (pintype "passive"))
      (node (ref "DD1") (pin "G8") (pinfunction "VCCPLL_G8") (pintype "power_in"))
      (node (ref "L5") (pin "2") (pinfunction "2_2") (pintype "passive"))
    )
    (net (code "21") (name "POR_B") (class "Default")
      (node (ref "DA1") (pin "4") (pinfunction "PG_4") (pintype "passive"))
      (node (ref "DA2") (pin "4") (pinfunction "PG_4") (pintype "passive"))
      (node (ref "DA3") (pin "4") (pinfunction "PG_4") (pintype "passive"))
    )
    (net (code "22") (name "VDD_1V0") (class "Default")
      (node (ref "C28") (pin "2") (pinfunction "2_2") (pintype "passive"))
      (node (ref "C29") (pin "2") (pinfunction "2_2") (pintype "passive"))
      (node (ref "C30") (pin "1") (pinfunction "1_1") (pintype "passive"))
      (node (ref "C31") (pin "1") (pinfunction "1_1") (pintype "passive"))
      (node (ref "C32") (pin "1") (pinfunction "1_1") (pintype "passive"))
      (node (ref "C33") (pin "1") (pinfunction "1_1") (pintype "passive"))
      (node (ref "C34") (pin "1") (pinfunction "1_1") (pintype "passive"))
      (node (ref "C38") (pin "1") (pinfunction "1_1") (pintype "passive"))
      (node (ref "C39") (pin "1") (pinfunction "1_1") (pintype "passive"))
      (node (ref "C40") (pin "1") (pinfunction "1_1") (pintype "passive"))
      (node (ref "C41") (pin "1") (pinfunction "1_1") (pintype "passive"))
      (node (ref "C42") (pin "1") (pinfunction "1_1") (pintype "passive"))
      (node (ref "C43") (pin "1") (pinfunction "1_1") (pintype "passive"))
      (node (ref "C44") (pin "1") (pinfunction "1_1") (pintype "passive"))
      (node (ref "C45") (pin "1") (pinfunction "1_1") (pintype "passive"))
      (node (ref "DD1") (pin "G11") (pinfunction "VCCBRAM_G11") (pintype "power_in"))
      (node (ref "DD1") (pin "G7") (pinfunction "VCCPINT_G7") (pintype "power_in"))
      (node (ref "DD1") (pin "H10") (pinfunction "VCCBRAM_H10") (pintype "power_in"))
      (node (ref "DD1") (pin "H12") (pinfunction "VCCINT_H12") (pintype "power_in"))
      (node (ref "DD1") (pin "J13") (pinfunction "VCCINT_J13") (pintype "power_in"))
      (node (ref "DD1") (pin "J7") (pinfunction "VCCPINT_J7") (pintype "power_in"))
      (node (ref "DD1") (pin "K12") (pinfunction "VCCINT_K12") (pintype "power_in"))
      (node (ref "DD1") (pin "L13") (pinfunction "VCCINT_L13") (pintype "power_in"))
      (node (ref "DD1") (pin "L7") (pinfunction "VCCPINT_L7") (pintype "power_in"))
      (node (ref "DD1") (pin "M12") (pinfunction "VCCINT_M12") (pintype "power_in"))
      (node (ref "DD1") (pin "N13") (pinfunction "VCCINT_N13") (pintype "power_in"))
      (node (ref "DD1") (pin "N7") (pinfunction "VCCPINT_N7") (pintype "power_in"))
      (node (ref "DD1") (pin "P12") (pinfunction "VCCINT_P12") (pintype "power_in"))
      (node (ref "DD1") (pin "P8") (pinfunction "VCCPINT_P8") (pintype "power_in"))
      (node (ref "DD1") (pin "R13") (pinfunction "VCCINT_R13") (pintype "power_in"))
      (node (ref "DD1") (pin "R7") (pinfunction "VCCPINT_R7") (pintype "power_in"))
      (node (ref "L4") (pin "1") (pinfunction "1_1") (pintype "passive"))
      (node (ref "R9") (pin "1") (pinfunction "1_1") (pintype "passive"))
    )
    (net (code "23") (name "VDD_1V8") (class "Default")
      (node (ref "C15") (pin "2") (pinfunction "2_2") (pintype "passive"))
      (node (ref "C16") (pin "2") (pinfunction "2_2") (pintype "passive"))
      (node (ref "C20") (pin "1") (pinfunction "1_1") (pintype "passive"))
      (node (ref "C21") (pin "1") (pinfunction "1_1") (pintype "passive"))
      (node (ref "C22") (pin "1") (pinfunction "1_1") (pintype "passive"))
      (node (ref "C23") (pin "1") (pinfunction "1_1") (pintype "passive"))
      (node (ref "C24") (pin "1") (pinfunction "1_1") (pintype "passive"))
      (node (ref "C35") (pin "1") (pinfunction "1_1") (pintype "passive"))
      (node (ref "C36") (pin "1") (pinfunction "1_1") (pintype "passive"))
      (node (ref "C37") (pin "1") (pinfunction "1_1") (pintype "passive"))
      (node (ref "DD1") (pin "F8") (pinfunction "VCCPAUX_F8") (pintype "power_in"))
      (node (ref "DD1") (pin "G9") (pinfunction "VCCPAUX_G9") (pintype "power_in"))
      (node (ref "DD1") (pin "H8") (pinfunction "VCCPAUX_H8") (pintype "power_in"))
      (node (ref "DD1") (pin "J11") (pinfunction "VCCAUX_J11") (pintype "power_in"))
      (node (ref "DD1") (pin "K8") (pinfunction "VCCPAUX_K8") (pintype "power_in"))
      (node (ref "DD1") (pin "L11") (pinfunction "VCCAUX_L11") (pintype "power_in"))
      (node (ref "DD1") (pin "M8") (pinfunction "VCCPAUX_M8") (pintype "power_in"))
      (node (ref "DD1") (pin "N11") (pinfunction "VCCAUX_N11") (pintype "power_in"))
      (node (ref "DD1") (pin "N9") (pinfunction "VCCAUX_N9") (pintype "power_in"))
      (node (ref "DD1") (pin "P10") (pinfunction "VCCAUX_P10") (pintype "power_in"))
      (node (ref "DD1") (pin "R9") (pinfunction "VCCAUX_R9") (pintype "power_in"))
      (node (ref "L3") (pin "1") (pinfunction "1_1") (pintype "passive"))
      (node (ref "L5") (pin "1") (pinfunction "1_1") (pintype "passive"))
      (node (ref "R6") (pin "1") (pinfunction "1_1") (pintype "passive"))
    )
    (net (code "24") (name "VDD_2V5") (class "Default")
      (node (ref "C10") (pin "2") (pinfunction "2_2") (pintype "passive"))
      (node (ref "C9") (pin "2") (pinfunction "2_2") (pintype "passive"))
      (node (ref "L2") (pin "1") (pinfunction "1_1") (pintype "passive"))
      (node (ref "R4") (pin "1") (pinfunction "1_1") (pintype "passive"))
    )
    (net (code "25") (name "VDD_3V3") (class "Default")
      (node (ref "C4") (pin "2") (pinfunction "2_2") (pintype "passive"))
      (node (ref "C5") (pin "2") (pinfunction "2_2") (pintype "passive"))
      (node (ref "L1") (pin "1") (pinfunction "1_1") (pintype "passive"))
      (node (ref "R2") (pin "1") (pinfunction "1_1") (pintype "passive"))
    )
    (net (code "26") (name "VDD_5V0") (class "Default")
      (node (ref "C13") (pin "2") (pinfunction "2_2") (pintype "passive"))
      (node (ref "C2") (pin "2") (pinfunction "2_2") (pintype "passive"))
      (node (ref "C25") (pin "2") (pinfunction "2_2") (pintype "passive"))
      (node (ref "C7") (pin "2") (pinfunction "2_2") (pintype "passive"))
      (node (ref "DA1") (pin "3") (pinfunction "VIN_3") (pintype "passive"))
      (node (ref "DA2") (pin "3") (pinfunction "VIN_3") (pintype "passive"))
      (node (ref "DA3") (pin "3") (pinfunction "VIN_3") (pintype "passive"))
      (node (ref "DA4") (pin "3") (pinfunction "EN_3") (pintype "passive"))
      (node (ref "DA4") (pin "5") (pinfunction "VIN_5") (pintype "passive"))
      (node (ref "DA4") (pin "6") (pinfunction "VIN_6") (pintype "passive"))
      (node (ref "R1") (pin "1") (pinfunction "1_1") (pintype "passive"))
    )
    (net (code "27") (name "unconnected-(DD1G-VCCINT-PadG13)") (class "Default")
      (node (ref "DD1") (pin "G13") (pinfunction "VCCINT_G13") (pintype "power_in"))
    )
  )
)
